# PowerModul.net
KiCad netlist of a schematic drawn in Altium Designer
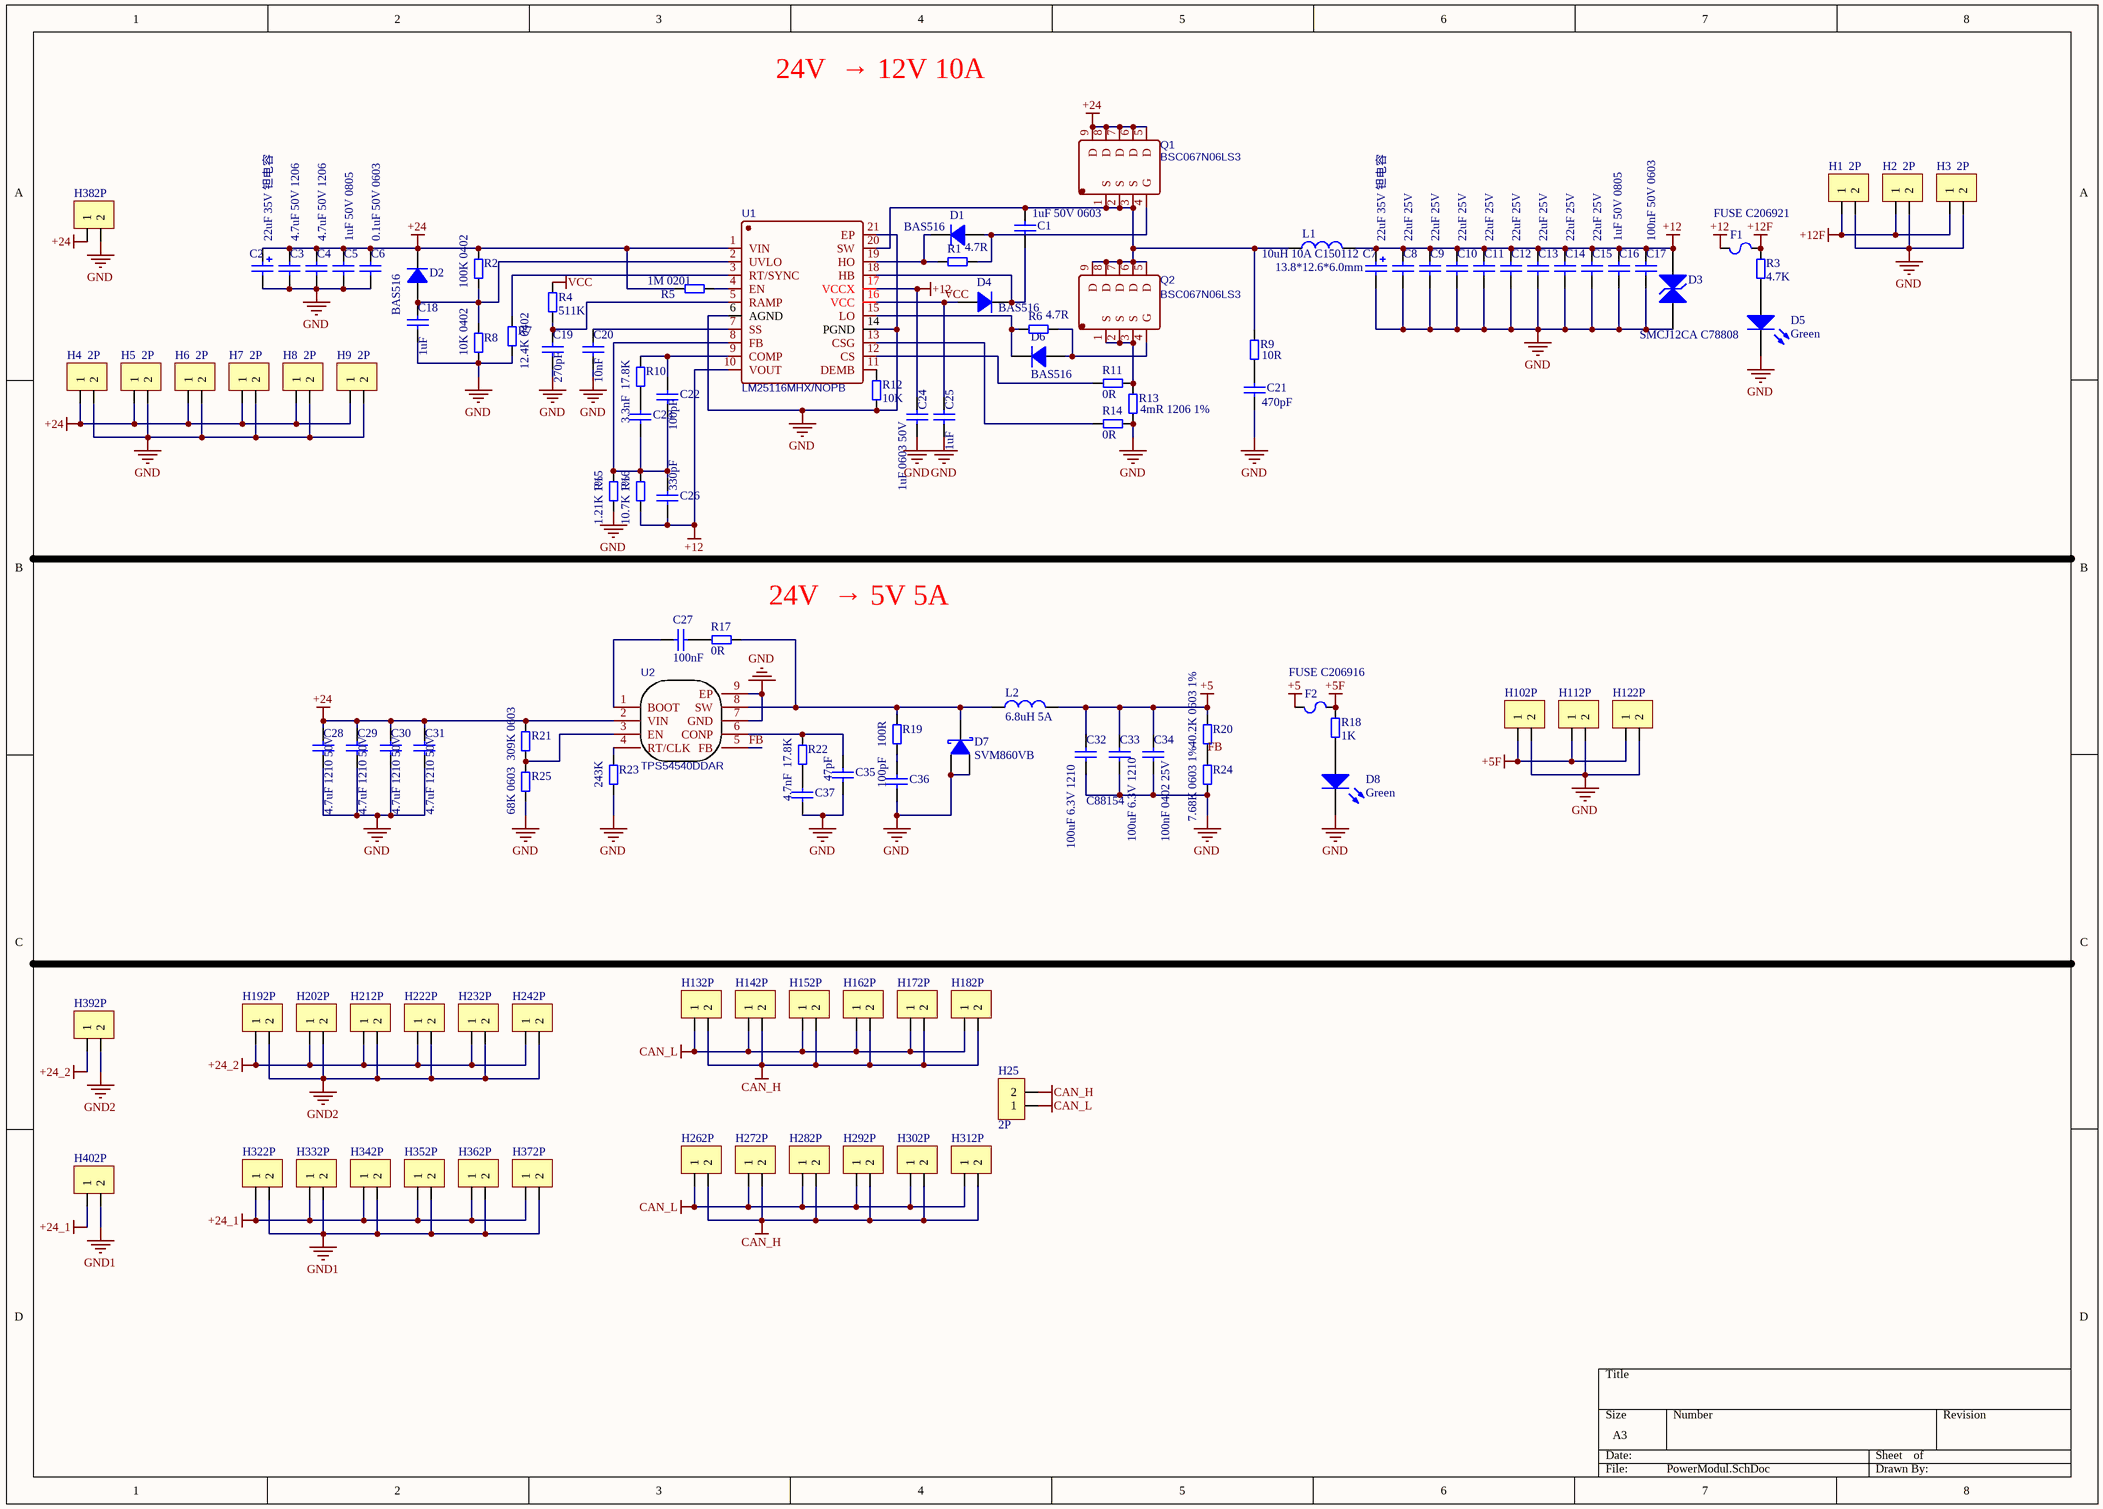
[diagram p0: PowerModul.SchDoc]

(export (version "E")
  (design (tool "Eeschema 10.0.6"))
  (components
    (comp (ref "C1")
      (value "1uF 50V 0603")
      (footprint "0603_C")
      (description "贴片电容")
      (libsource (lib "WTR-SCH_LIB") (part "C"))
    )
    (comp (ref "C2")
      (value "22uF 35V 钽电容")
      (footprint "CAP-SMD_L7.3-W4.3-R-RD")
      (description "极性电容")
      (libsource (lib "WTR-SCH_LIB") (part "Cp"))
    )
    (comp (ref "C3")
      (value "4.7uF 50V 1206")
      (footprint "1206_C")
      (description "贴片电容")
      (libsource (lib "WTR-SCH_LIB") (part "C"))
    )
    (comp (ref "C4")
      (value "4.7uF 50V 1206")
      (footprint "1206_C")
      (description "贴片电容")
      (libsource (lib "WTR-SCH_LIB") (part "C"))
    )
    (comp (ref "C5")
      (value "1uF 50V 0805")
      (footprint "0805_C")
      (description "贴片电容")
      (libsource (lib "WTR-SCH_LIB") (part "C"))
    )
    (comp (ref "C6")
      (value "0.1uF 50V 0603")
      (footprint "0603_C")
      (description "贴片电容")
      (libsource (lib "WTR-SCH_LIB") (part "C"))
    )
    (comp (ref "C7")
      (value "22uF 35V 钽电容")
      (footprint "CAP-SMD_L7.3-W4.3-R-RD")
      (description "极性电容")
      (libsource (lib "WTR-SCH_LIB") (part "Cp"))
    )
    (comp (ref "C8")
      (value "22uF 25V")
      (footprint "1206_C")
      (description "贴片电容")
      (libsource (lib "WTR-SCH_LIB") (part "C"))
    )
    (comp (ref "C9")
      (value "22uF 25V")
      (footprint "1206_C")
      (description "贴片电容")
      (libsource (lib "WTR-SCH_LIB") (part "C"))
    )
    (comp (ref "C10")
      (value "22uF 25V")
      (footprint "1206_C")
      (description "贴片电容")
      (libsource (lib "WTR-SCH_LIB") (part "C"))
    )
    (comp (ref "C11")
      (value "22uF 25V")
      (footprint "1206_C")
      (description "贴片电容")
      (libsource (lib "WTR-SCH_LIB") (part "C"))
    )
    (comp (ref "C12")
      (value "22uF 25V")
      (footprint "1206_C")
      (description "贴片电容")
      (libsource (lib "WTR-SCH_LIB") (part "C"))
    )
    (comp (ref "C13")
      (value "22uF 25V")
      (footprint "1206_C")
      (description "贴片电容")
      (libsource (lib "WTR-SCH_LIB") (part "C"))
    )
    (comp (ref "C14")
      (value "22uF 25V")
      (footprint "1206_C")
      (description "贴片电容")
      (libsource (lib "WTR-SCH_LIB") (part "C"))
    )
    (comp (ref "C15")
      (value "22uF 25V")
      (footprint "1206_C")
      (description "贴片电容")
      (libsource (lib "WTR-SCH_LIB") (part "C"))
    )
    (comp (ref "C16")
      (value "1uF 50V 0805")
      (footprint "0805_C")
      (description "贴片电容")
      (libsource (lib "WTR-SCH_LIB") (part "C"))
    )
    (comp (ref "C17")
      (value "100nF 50V 0603")
      (footprint "0603_C")
      (description "贴片电容")
      (libsource (lib "WTR-SCH_LIB") (part "C"))
    )
    (comp (ref "C18")
      (value "1uF")
      (footprint "0402_C")
      (description "贴片电容")
      (libsource (lib "WTR-SCH_LIB") (part "C"))
    )
    (comp (ref "C19")
      (value "270pF")
      (footprint "0402_C")
      (description "贴片电容")
      (libsource (lib "WTR-SCH_LIB") (part "C"))
    )
    (comp (ref "C20")
      (value "10nF")
      (footprint "0402_C")
      (description "贴片电容")
      (libsource (lib "WTR-SCH_LIB") (part "C"))
    )
    (comp (ref "C21")
      (value "470pF")
      (footprint "0402_C")
      (description "贴片电容")
      (libsource (lib "WTR-SCH_LIB") (part "C"))
    )
    (comp (ref "C22")
      (value "100pF")
      (footprint "0402_C")
      (description "贴片电容")
      (libsource (lib "WTR-SCH_LIB") (part "C"))
    )
    (comp (ref "C23")
      (value "3.3nF")
      (footprint "0402_C")
      (description "贴片电容")
      (libsource (lib "WTR-SCH_LIB") (part "C"))
    )
    (comp (ref "C24")
      (value "1uF 0603 50V")
      (footprint "0603_C")
      (description "贴片电容")
      (libsource (lib "WTR-SCH_LIB") (part "C"))
    )
    (comp (ref "C25")
      (value "1uF")
      (footprint "0402_C")
      (description "贴片电容")
      (libsource (lib "WTR-SCH_LIB") (part "C"))
    )
    (comp (ref "C26")
      (value "330pF")
      (footprint "0402_C")
      (description "贴片电容")
      (libsource (lib "WTR-SCH_LIB") (part "C"))
    )
    (comp (ref "C27")
      (value "100nF")
      (footprint "0402_C")
      (description "贴片电容")
      (libsource (lib "WTR-SCH_LIB") (part "C"))
    )
    (comp (ref "C28")
      (value "4.7uF 1210 50V")
      (footprint "C1210")
      (description "贴片电容")
      (libsource (lib "WTR-SCH_LIB") (part "C"))
    )
    (comp (ref "C29")
      (value "4.7uF 1210 50V")
      (footprint "C1210")
      (description "贴片电容")
      (libsource (lib "WTR-SCH_LIB") (part "C"))
    )
    (comp (ref "C30")
      (value "4.7uF 1210 50V")
      (footprint "C1210")
      (description "贴片电容")
      (libsource (lib "WTR-SCH_LIB") (part "C"))
    )
    (comp (ref "C31")
      (value "4.7uF 1210 50V")
      (footprint "C1210")
      (description "贴片电容")
      (libsource (lib "WTR-SCH_LIB") (part "C"))
    )
    (comp (ref "C32")
      (value "100uF 6.3V 1210")
      (footprint "C1210")
      (description "贴片电容")
      (libsource (lib "WTR-SCH_LIB") (part "C"))
    )
    (comp (ref "C33")
      (value "100uF 6.3V 1210")
      (footprint "C1210")
      (description "贴片电容")
      (libsource (lib "WTR-SCH_LIB") (part "C"))
    )
    (comp (ref "C34")
      (value "100nF 0402 25V")
      (footprint "0402_C")
      (description "贴片电容")
      (libsource (lib "WTR-SCH_LIB") (part "C"))
    )
    (comp (ref "C35")
      (value "47pF")
      (footprint "0603_C")
      (description "贴片电容")
      (libsource (lib "WTR-SCH_LIB") (part "C"))
    )
    (comp (ref "C36")
      (value "100pF")
      (footprint "0603_C")
      (description "贴片电容")
      (libsource (lib "WTR-SCH_LIB") (part "C"))
    )
    (comp (ref "C37")
      (value "4.7nF")
      (footprint "0603_C")
      (description "贴片电容")
      (libsource (lib "WTR-SCH_LIB") (part "C"))
    )
    (comp (ref "D1")
      (value "BAS516")
      (footprint "SOD-523_L1.2-W0.8-LS1.6-RD")
      (description "二极管")
      (libsource (lib "WTR-SCH_LIB") (part "D"))
    )
    (comp (ref "D2")
      (value "BAS516")
      (footprint "SOD-523_L1.2-W0.8-LS1.6-RD")
      (description "二极管")
      (libsource (lib "WTR-SCH_LIB") (part "D"))
    )
    (comp (ref "D3")
      (value "SMCJ12CA C78808")
      (footprint "SMC_L6.9-W5.9-LS7.9-BI")
      (description "TVS")
      (libsource (lib "WTR-SCH_LIB") (part "TVS"))
    )
    (comp (ref "D4")
      (value "BAS516")
      (footprint "SOD-523_L1.2-W0.8-LS1.6-RD")
      (description "二极管")
      (libsource (lib "WTR-SCH_LIB") (part "D"))
    )
    (comp (ref "D5")
      (value "Green")
      (footprint "0805_LED_S1")
      (description "发光二极管")
      (libsource (lib "WTR-SCH_LIB") (part "LED"))
    )
    (comp (ref "D6")
      (value "BAS516")
      (footprint "SOD-523_L1.2-W0.8-LS1.6-RD")
      (description "二极管")
      (libsource (lib "WTR-SCH_LIB") (part "D"))
    )
    (comp (ref "D7")
      (value "SVM860VB")
      (footprint "TO-277B_3P-L6.1-W4.3-LS7.0-BR")
      (description "肖特基二极管")
      (libsource (lib "WTR-SCH_LIB") (part "Ds3"))
    )
    (comp (ref "D8")
      (value "Green")
      (footprint "0805_LED_S1")
      (description "发光二极管")
      (libsource (lib "WTR-SCH_LIB") (part "LED"))
    )
    (comp (ref "F1")
      (value "FUSE C206921")
      (footprint "FUSE-SMD_L9.8-W5.1")
      (description "熔断器")
      (libsource (lib "WTR-SCH_LIB") (part "FUSE"))
    )
    (comp (ref "F2")
      (value "FUSE C206916")
      (footprint "FUSE-SMD_L9.8-W5.1")
      (description "熔断器")
      (libsource (lib "WTR-SCH_LIB") (part "FUSE"))
    )
    (comp (ref "H1") (value "2P") (footprint "XT30UPB-F") (libsource (lib "WTR-SCH_LIB") (part "2P")))
    (comp (ref "H2") (value "2P") (footprint "XT30UPB-F") (libsource (lib "WTR-SCH_LIB") (part "2P")))
    (comp (ref "H3") (value "2P") (footprint "XT30UPB-F") (libsource (lib "WTR-SCH_LIB") (part "2P")))
    (comp (ref "H4") (value "2P") (footprint "XT30UPB-F") (libsource (lib "WTR-SCH_LIB") (part "2P")))
    (comp (ref "H5") (value "2P") (footprint "XT30UPB-F") (libsource (lib "WTR-SCH_LIB") (part "2P")))
    (comp (ref "H6") (value "2P") (footprint "XT30UPB-F") (libsource (lib "WTR-SCH_LIB") (part "2P")))
    (comp (ref "H7") (value "2P") (footprint "XT30UPB-F") (libsource (lib "WTR-SCH_LIB") (part "2P")))
    (comp (ref "H8") (value "2P") (footprint "XT30UPB-F") (libsource (lib "WTR-SCH_LIB") (part "2P")))
    (comp (ref "H9") (value "2P") (footprint "XT30UPB-F") (libsource (lib "WTR-SCH_LIB") (part "2P")))
    (comp (ref "H10") (value "2P") (footprint "XT30UPB-F") (libsource (lib "WTR-SCH_LIB") (part "2P")))
    (comp (ref "H11") (value "2P") (footprint "XT30UPB-F") (libsource (lib "WTR-SCH_LIB") (part "2P")))
    (comp (ref "H12") (value "2P") (footprint "XT30UPB-F") (libsource (lib "WTR-SCH_LIB") (part "2P")))
    (comp (ref "H13") (value "2P") (footprint "GH1.25-S-2P") (libsource (lib "WTR-SCH_LIB") (part "2P")))
    (comp (ref "H14") (value "2P") (footprint "GH1.25-S-2P") (libsource (lib "WTR-SCH_LIB") (part "2P")))
    (comp (ref "H15") (value "2P") (footprint "GH1.25-S-2P") (libsource (lib "WTR-SCH_LIB") (part "2P")))
    (comp (ref "H16") (value "2P") (footprint "GH1.25-S-2P") (libsource (lib "WTR-SCH_LIB") (part "2P")))
    (comp (ref "H17") (value "2P") (footprint "GH1.25-S-2P") (libsource (lib "WTR-SCH_LIB") (part "2P")))
    (comp (ref "H18") (value "2P") (footprint "GH1.25-S-2P") (libsource (lib "WTR-SCH_LIB") (part "2P")))
    (comp (ref "H19") (value "2P") (footprint "TX60-LI-P") (libsource (lib "WTR-SCH_LIB") (part "2P")))
    (comp (ref "H20") (value "2P") (footprint "TX60-LI-P") (libsource (lib "WTR-SCH_LIB") (part "2P")))
    (comp (ref "H21") (value "2P") (footprint "TX60-LI-P") (libsource (lib "WTR-SCH_LIB") (part "2P")))
    (comp (ref "H22") (value "2P") (footprint "TX60-LI-P") (libsource (lib "WTR-SCH_LIB") (part "2P")))
    (comp (ref "H23") (value "2P") (footprint "TX60-LI-P") (libsource (lib "WTR-SCH_LIB") (part "2P")))
    (comp (ref "H24") (value "2P") (footprint "TX60-LI-P") (libsource (lib "WTR-SCH_LIB") (part "2P")))
    (comp (ref "H25") (value "2P") (footprint "GH1.25-S-2P") (libsource (lib "") (part "2P_1")))
    (comp (ref "H26") (value "2P") (footprint "GH1.25-S-2P") (libsource (lib "WTR-SCH_LIB") (part "2P")))
    (comp (ref "H27") (value "2P") (footprint "GH1.25-S-2P") (libsource (lib "WTR-SCH_LIB") (part "2P")))
    (comp (ref "H28") (value "2P") (footprint "GH1.25-S-2P") (libsource (lib "WTR-SCH_LIB") (part "2P")))
    (comp (ref "H29") (value "2P") (footprint "GH1.25-S-2P") (libsource (lib "WTR-SCH_LIB") (part "2P")))
    (comp (ref "H30") (value "2P") (footprint "GH1.25-S-2P") (libsource (lib "WTR-SCH_LIB") (part "2P")))
    (comp (ref "H31") (value "2P") (footprint "GH1.25-S-2P") (libsource (lib "WTR-SCH_LIB") (part "2P")))
    (comp (ref "H32") (value "2P") (footprint "TX60-LI-P") (libsource (lib "WTR-SCH_LIB") (part "2P")))
    (comp (ref "H33") (value "2P") (footprint "TX60-LI-P") (libsource (lib "WTR-SCH_LIB") (part "2P")))
    (comp (ref "H34") (value "2P") (footprint "TX60-LI-P") (libsource (lib "WTR-SCH_LIB") (part "2P")))
    (comp (ref "H35") (value "2P") (footprint "TX60-LI-P") (libsource (lib "WTR-SCH_LIB") (part "2P")))
    (comp (ref "H36") (value "2P") (footprint "TX60-LI-P") (libsource (lib "WTR-SCH_LIB") (part "2P")))
    (comp (ref "H37") (value "2P") (footprint "TX60-LI-P") (libsource (lib "WTR-SCH_LIB") (part "2P")))
    (comp (ref "H38") (value "2P") (footprint "TX60PW-M20") (libsource (lib "WTR-SCH_LIB") (part "2P")))
    (comp (ref "H39") (value "2P") (footprint "TX60PW-M20") (libsource (lib "WTR-SCH_LIB") (part "2P")))
    (comp (ref "H40") (value "2P") (footprint "TX60PW-M20") (libsource (lib "WTR-SCH_LIB") (part "2P")))
    (comp (ref "L1")
      (value "10uH 10A C150112")
      (footprint "IND-SMD_L13.8-W12.6_SMMS1360")
      (description "电感")
      (libsource (lib "WTR-SCH_LIB") (part "L"))
    )
    (comp (ref "L2")
      (value "6.8uH 5A")
      (footprint "IND-SMD_L7.1-W6.6")
      (description "电感")
      (libsource (lib "WTR-SCH_LIB") (part "L"))
    )
    (comp (ref "Q1")
      (value "BSC067N06LS3")
      (footprint "PG-TDSON-8_L5.0-W6.0-P1.27-LS6.2-BL-EP")
      (fields
        (field (name "BOM_SUPPLIER PART") "C140227")
        (field (name "BOM_MANUFACTURER PART") "CSD18563Q5AT")
        (field (name "CONTRIBUTOR") "LCSC")
      )
      (libsource (lib "WTR-SCH_LIB") (part "CSD18563Q5AT"))
    )
    (comp (ref "Q2")
      (value "BSC067N06LS3")
      (footprint "PG-TDSON-8_L5.0-W6.0-P1.27-LS6.2-BL-EP")
      (fields
        (field (name "BOM_SUPPLIER PART") "C140227")
        (field (name "BOM_MANUFACTURER PART") "CSD18563Q5AT")
        (field (name "CONTRIBUTOR") "LCSC")
      )
      (libsource (lib "WTR-SCH_LIB") (part "CSD18563Q5AT"))
    )
    (comp (ref "R1")
      (value "4.7R")
      (footprint "0402_R")
      (description "贴片电阻")
      (libsource (lib "WTR-SCH_LIB") (part "R"))
    )
    (comp (ref "R2")
      (value "100K 0402")
      (footprint "0402_R")
      (description "贴片电阻")
      (libsource (lib "WTR-SCH_LIB") (part "R"))
    )
    (comp (ref "R3")
      (value "4.7K")
      (footprint "0402_R")
      (description "贴片电阻")
      (libsource (lib "WTR-SCH_LIB") (part "R"))
    )
    (comp (ref "R4")
      (value "511K")
      (footprint "0402_R")
      (description "贴片电阻")
      (libsource (lib "WTR-SCH_LIB") (part "R"))
    )
    (comp (ref "R5")
      (value "1M 0201")
      (footprint "0402_R")
      (description "贴片电阻")
      (libsource (lib "WTR-SCH_LIB") (part "R"))
    )
    (comp (ref "R6")
      (value "4.7R")
      (footprint "0402_R")
      (description "贴片电阻")
      (libsource (lib "WTR-SCH_LIB") (part "R"))
    )
    (comp (ref "R7")
      (value "12.4K 0402")
      (footprint "0402_R")
      (description "贴片电阻")
      (libsource (lib "WTR-SCH_LIB") (part "R"))
    )
    (comp (ref "R8")
      (value "10K 0402")
      (footprint "0402_R")
      (description "贴片电阻")
      (libsource (lib "WTR-SCH_LIB") (part "R"))
    )
    (comp (ref "R9")
      (value "10R")
      (footprint "0402_R")
      (description "贴片电阻")
      (libsource (lib "WTR-SCH_LIB") (part "R"))
    )
    (comp (ref "R10")
      (value "17.8K")
      (footprint "0402_R")
      (description "贴片电阻")
      (libsource (lib "WTR-SCH_LIB") (part "R"))
    )
    (comp (ref "R11")
      (value "0R")
      (footprint "0402_R")
      (description "贴片电阻")
      (libsource (lib "WTR-SCH_LIB") (part "R"))
    )
    (comp (ref "R12")
      (value "10K")
      (footprint "0402_R")
      (description "贴片电阻")
      (libsource (lib "WTR-SCH_LIB") (part "R"))
    )
    (comp (ref "R13")
      (value "4mR 1206 1%")
      (footprint "1206_R")
      (description "贴片电阻")
      (libsource (lib "WTR-SCH_LIB") (part "R"))
    )
    (comp (ref "R14")
      (value "0R")
      (footprint "0402_R")
      (description "贴片电阻")
      (libsource (lib "WTR-SCH_LIB") (part "R"))
    )
    (comp (ref "R15")
      (value "1.21K 1%")
      (footprint "0402_R")
      (description "贴片电阻")
      (libsource (lib "WTR-SCH_LIB") (part "R"))
    )
    (comp (ref "R16")
      (value "10.7K 1%")
      (footprint "0402_R")
      (description "贴片电阻")
      (libsource (lib "WTR-SCH_LIB") (part "R"))
    )
    (comp (ref "R17")
      (value "0R")
      (footprint "0402_R")
      (description "贴片电阻")
      (libsource (lib "WTR-SCH_LIB") (part "R"))
    )
    (comp (ref "R18")
      (value "1K")
      (footprint "0402_R")
      (description "贴片电阻")
      (libsource (lib "WTR-SCH_LIB") (part "R"))
    )
    (comp (ref "R19")
      (value "100R")
      (footprint "0402_R")
      (description "贴片电阻")
      (libsource (lib "WTR-SCH_LIB") (part "R"))
    )
    (comp (ref "R20")
      (value "40.2K 0603 1%")
      (footprint "0603_R")
      (description "贴片电阻")
      (libsource (lib "WTR-SCH_LIB") (part "R"))
    )
    (comp (ref "R21")
      (value "309K 0603")
      (footprint "0603_R")
      (description "贴片电阻")
      (libsource (lib "WTR-SCH_LIB") (part "R"))
    )
    (comp (ref "R22")
      (value "17.8K")
      (footprint "0402_R")
      (description "贴片电阻")
      (libsource (lib "WTR-SCH_LIB") (part "R"))
    )
    (comp (ref "R23")
      (value "243K")
      (footprint "0402_R")
      (description "贴片电阻")
      (libsource (lib "WTR-SCH_LIB") (part "R"))
    )
    (comp (ref "R24")
      (value "7.68K 0603 1%")
      (footprint "0603_R")
      (description "贴片电阻")
      (libsource (lib "WTR-SCH_LIB") (part "R"))
    )
    (comp (ref "R25")
      (value "68K 0603")
      (footprint "0603_R")
      (description "贴片电阻")
      (libsource (lib "WTR-SCH_LIB") (part "R"))
    )
    (comp (ref "U1")
      (value "LM25116MHX/NOPB")
      (footprint "HTSSOP-20_L6.5-W4.4-P0.65-LS6.4-BL-EP")
      (fields (field (name "BOM_SUPPLIER PART") "C390951") (field (name "CONTRIBUTOR") "LCSC"))
      (libsource (lib "Sheet_2_2020-07-13_16-15-20") (part "LM25116MHX/NOPB"))
    )
    (comp (ref "U2")
      (value "TPS54540DDAR")
      (footprint "SOIC-8-EP")
      (fields (field (name "BOM_SUPPLIER PART") "C95286"))
      (libsource (lib "WTR-SCH_LIB") (part "TPS54540DDAR"))
    )
  )
  (nets
    (net (code "1") (name "+5") (class "Default")
      (node (ref "C32") (pin "2") (pinfunction "2_2") (pintype "passive"))
      (node (ref "C33") (pin "2") (pinfunction "2_2") (pintype "passive"))
      (node (ref "C34") (pin "2") (pinfunction "2_2") (pintype "passive"))
      (node (ref "F2") (pin "1") (pinfunction "1_1") (pintype "passive"))
      (node (ref "L2") (pin "2") (pinfunction "2_2") (pintype "passive"))
      (node (ref "R20") (pin "1") (pinfunction "1_1") (pintype "passive"))
    )
    (net (code "2") (name "+5F") (class "Default")
      (node (ref "F2") (pin "2") (pinfunction "2_2") (pintype "passive"))
      (node (ref "H10") (pin "1") (pinfunction "1_1") (pintype "passive"))
      (node (ref "H11") (pin "1") (pinfunction "1_1") (pintype "passive"))
      (node (ref "H12") (pin "1") (pinfunction "1_1") (pintype "passive"))
      (node (ref "R18") (pin "1") (pinfunction "1_1") (pintype "passive"))
    )
    (net (code "3") (name "+12") (class "Default")
      (node (ref "C10") (pin "2") (pinfunction "2_2") (pintype "passive"))
      (node (ref "C11") (pin "2") (pinfunction "2_2") (pintype "passive"))
      (node (ref "C12") (pin "2") (pinfunction "2_2") (pintype "passive"))
      (node (ref "C13") (pin "2") (pinfunction "2_2") (pintype "passive"))
      (node (ref "C14") (pin "2") (pinfunction "2_2") (pintype "passive"))
      (node (ref "C15") (pin "2") (pinfunction "2_2") (pintype "passive"))
      (node (ref "C16") (pin "2") (pinfunction "2_2") (pintype "passive"))
      (node (ref "C17") (pin "2") (pinfunction "2_2") (pintype "passive"))
      (node (ref "C24") (pin "2") (pinfunction "2_2") (pintype "passive"))
      (node (ref "C26") (pin "1") (pinfunction "1_1") (pintype "passive"))
      (node (ref "C7") (pin "1") (pinfunction "1_1") (pintype "passive"))
      (node (ref "C8") (pin "2") (pinfunction "2_2") (pintype "passive"))
      (node (ref "C9") (pin "2") (pinfunction "2_2") (pintype "passive"))
      (node (ref "D3") (pin "2") (pinfunction "K_2") (pintype "passive"))
      (node (ref "F1") (pin "1") (pinfunction "1_1") (pintype "passive"))
      (node (ref "L1") (pin "2") (pinfunction "2_2") (pintype "passive"))
      (node (ref "R16") (pin "2") (pinfunction "2_2") (pintype "passive"))
      (node (ref "U1") (pin "10") (pinfunction "VOUT_10") (pintype "passive"))
      (node (ref "U1") (pin "17") (pinfunction "VCCX_17") (pintype "passive"))
    )
    (net (code "4") (name "+12F") (class "Default")
      (node (ref "F1") (pin "2") (pinfunction "2_2") (pintype "passive"))
      (node (ref "H1") (pin "1") (pinfunction "1_1") (pintype "passive"))
      (node (ref "H2") (pin "1") (pinfunction "1_1") (pintype "passive"))
      (node (ref "H3") (pin "1") (pinfunction "1_1") (pintype "passive"))
      (node (ref "R3") (pin "1") (pinfunction "1_1") (pintype "passive"))
    )
    (net (code "5") (name "+24") (class "Default")
      (node (ref "C2") (pin "1") (pinfunction "1_1") (pintype "passive"))
      (node (ref "C28") (pin "2") (pinfunction "2_2") (pintype "passive"))
      (node (ref "C29") (pin "2") (pinfunction "2_2") (pintype "passive"))
      (node (ref "C3") (pin "2") (pinfunction "2_2") (pintype "passive"))
      (node (ref "C30") (pin "2") (pinfunction "2_2") (pintype "passive"))
      (node (ref "C31") (pin "2") (pinfunction "2_2") (pintype "passive"))
      (node (ref "C4") (pin "2") (pinfunction "2_2") (pintype "passive"))
      (node (ref "C5") (pin "2") (pinfunction "2_2") (pintype "passive"))
      (node (ref "C6") (pin "2") (pinfunction "2_2") (pintype "passive"))
      (node (ref "D2") (pin "2") (pinfunction "K_2") (pintype "passive"))
      (node (ref "H38") (pin "1") (pinfunction "1_1") (pintype "passive"))
      (node (ref "H4") (pin "1") (pinfunction "1_1") (pintype "passive"))
      (node (ref "H5") (pin "1") (pinfunction "1_1") (pintype "passive"))
      (node (ref "H6") (pin "1") (pinfunction "1_1") (pintype "passive"))
      (node (ref "H7") (pin "1") (pinfunction "1_1") (pintype "passive"))
      (node (ref "H8") (pin "1") (pinfunction "1_1") (pintype "passive"))
      (node (ref "H9") (pin "1") (pinfunction "1_1") (pintype "passive"))
      (node (ref "Q1") (pin "5") (pinfunction "D_5") (pintype "passive"))
      (node (ref "Q1") (pin "6") (pinfunction "D_6") (pintype "passive"))
      (node (ref "Q1") (pin "7") (pinfunction "D_7") (pintype "passive"))
      (node (ref "Q1") (pin "8") (pinfunction "D_8") (pintype "passive"))
      (node (ref "Q1") (pin "9") (pinfunction "D_9") (pintype "passive"))
      (node (ref "R2") (pin "2") (pinfunction "2_2") (pintype "passive"))
      (node (ref "R21") (pin "2") (pinfunction "2_2") (pintype "passive"))
      (node (ref "R5") (pin "2") (pinfunction "2_2") (pintype "passive"))
      (node (ref "U1") (pin "1") (pinfunction "VIN_1") (pintype "passive"))
      (node (ref "U2") (pin "2") (pinfunction "VIN_2") (pintype "passive"))
    )
    (net (code "6") (name "+24_1") (class "Default")
      (node (ref "H32") (pin "1") (pinfunction "1_1") (pintype "passive"))
      (node (ref "H33") (pin "1") (pinfunction "1_1") (pintype "passive"))
      (node (ref "H34") (pin "1") (pinfunction "1_1") (pintype "passive"))
      (node (ref "H35") (pin "1") (pinfunction "1_1") (pintype "passive"))
      (node (ref "H36") (pin "1") (pinfunction "1_1") (pintype "passive"))
      (node (ref "H37") (pin "1") (pinfunction "1_1") (pintype "passive"))
      (node (ref "H40") (pin "1") (pinfunction "1_1") (pintype "passive"))
    )
    (net (code "7") (name "+24_2") (class "Default")
      (node (ref "H19") (pin "1") (pinfunction "1_1") (pintype "passive"))
      (node (ref "H20") (pin "1") (pinfunction "1_1") (pintype "passive"))
      (node (ref "H21") (pin "1") (pinfunction "1_1") (pintype "passive"))
      (node (ref "H22") (pin "1") (pinfunction "1_1") (pintype "passive"))
      (node (ref "H23") (pin "1") (pinfunction "1_1") (pintype "passive"))
      (node (ref "H24") (pin "1") (pinfunction "1_1") (pintype "passive"))
      (node (ref "H39") (pin "1") (pinfunction "1_1") (pintype "passive"))
    )
    (net (code "8") (name "/FB") (class "Default")
      (node (ref "R20") (pin "2") (pinfunction "2_2") (pintype "passive"))
      (node (ref "R24") (pin "1") (pinfunction "1_1") (pintype "passive"))
      (node (ref "U2") (pin "5") (pinfunction "FB_5") (pintype "passive"))
    )
    (net (code "9") (name "CAN_H") (class "Default")
      (node (ref "H13") (pin "2") (pinfunction "2_2") (pintype "passive"))
      (node (ref "H14") (pin "2") (pinfunction "2_2") (pintype "passive"))
      (node (ref "H15") (pin "2") (pinfunction "2_2") (pintype "passive"))
      (node (ref "H16") (pin "2") (pinfunction "2_2") (pintype "passive"))
      (node (ref "H17") (pin "2") (pinfunction "2_2") (pintype "passive"))
      (node (ref "H18") (pin "2") (pinfunction "2_2") (pintype "passive"))
      (node (ref "H25") (pin "2") (pinfunction "2_2") (pintype "passive"))
      (node (ref "H26") (pin "2") (pinfunction "2_2") (pintype "passive"))
      (node (ref "H27") (pin "2") (pinfunction "2_2") (pintype "passive"))
      (node (ref "H28") (pin "2") (pinfunction "2_2") (pintype "passive"))
      (node (ref "H29") (pin "2") (pinfunction "2_2") (pintype "passive"))
      (node (ref "H30") (pin "2") (pinfunction "2_2") (pintype "passive"))
      (node (ref "H31") (pin "2") (pinfunction "2_2") (pintype "passive"))
    )
    (net (code "10") (name "CAN_L") (class "Default")
      (node (ref "H13") (pin "1") (pinfunction "1_1") (pintype "passive"))
      (node (ref "H14") (pin "1") (pinfunction "1_1") (pintype "passive"))
      (node (ref "H15") (pin "1") (pinfunction "1_1") (pintype "passive"))
      (node (ref "H16") (pin "1") (pinfunction "1_1") (pintype "passive"))
      (node (ref "H17") (pin "1") (pinfunction "1_1") (pintype "passive"))
      (node (ref "H18") (pin "1") (pinfunction "1_1") (pintype "passive"))
      (node (ref "H25") (pin "1") (pinfunction "1_1") (pintype "passive"))
      (node (ref "H26") (pin "1") (pinfunction "1_1") (pintype "passive"))
      (node (ref "H27") (pin "1") (pinfunction "1_1") (pintype "passive"))
      (node (ref "H28") (pin "1") (pinfunction "1_1") (pintype "passive"))
      (node (ref "H29") (pin "1") (pinfunction "1_1") (pintype "passive"))
      (node (ref "H30") (pin "1") (pinfunction "1_1") (pintype "passive"))
      (node (ref "H31") (pin "1") (pinfunction "1_1") (pintype "passive"))
    )
    (net (code "11") (name "GND") (class "Default")
      (node (ref "C10") (pin "1") (pinfunction "1_1") (pintype "passive"))
      (node (ref "C11") (pin "1") (pinfunction "1_1") (pintype "passive"))
      (node (ref "C12") (pin "1") (pinfunction "1_1") (pintype "passive"))
      (node (ref "C13") (pin "1") (pinfunction "1_1") (pintype "passive"))
      (node (ref "C14") (pin "1") (pinfunction "1_1") (pintype "passive"))
      (node (ref "C15") (pin "1") (pinfunction "1_1") (pintype "passive"))
      (node (ref "C16") (pin "1") (pinfunction "1_1") (pintype "passive"))
      (node (ref "C17") (pin "1") (pinfunction "1_1") (pintype "passive"))
      (node (ref "C18") (pin "1") (pinfunction "1_1") (pintype "passive"))
      (node (ref "C19") (pin "1") (pinfunction "1_1") (pintype "passive"))
      (node (ref "C2") (pin "2") (pinfunction "2_2") (pintype "passive"))
      (node (ref "C20") (pin "1") (pinfunction "1_1") (pintype "passive"))
      (node (ref "C21") (pin "1") (pinfunction "1_1") (pintype "passive"))
      (node (ref "C24") (pin "1") (pinfunction "1_1") (pintype "passive"))
      (node (ref "C25") (pin "1") (pinfunction "1_1") (pintype "passive"))
      (node (ref "C28") (pin "1") (pinfunction "1_1") (pintype "passive"))
      (node (ref "C29") (pin "1") (pinfunction "1_1") (pintype "passive"))
      (node (ref "C3") (pin "1") (pinfunction "1_1") (pintype "passive"))
      (node (ref "C30") (pin "1") (pinfunction "1_1") (pintype "passive"))
      (node (ref "C31") (pin "1") (pinfunction "1_1") (pintype "passive"))
      (node (ref "C32") (pin "1") (pinfunction "1_1") (pintype "passive"))
      (node (ref "C33") (pin "1") (pinfunction "1_1") (pintype "passive"))
      (node (ref "C34") (pin "1") (pinfunction "1_1") (pintype "passive"))
      (node (ref "C35") (pin "1") (pinfunction "1_1") (pintype "passive"))
      (node (ref "C36") (pin "1") (pinfunction "1_1") (pintype "passive"))
      (node (ref "C37") (pin "1") (pinfunction "1_1") (pintype "passive"))
      (node (ref "C4") (pin "1") (pinfunction "1_1") (pintype "passive"))
      (node (ref "C5") (pin "1") (pinfunction "1_1") (pintype "passive"))
      (node (ref "C6") (pin "1") (pinfunction "1_1") (pintype "passive"))
      (node (ref "C7") (pin "2") (pinfunction "2_2") (pintype "passive"))
      (node (ref "C8") (pin "1") (pinfunction "1_1") (pintype "passive"))
      (node (ref "C9") (pin "1") (pinfunction "1_1") (pintype "passive"))
      (node (ref "D3") (pin "1") (pinfunction "A_1") (pintype "passive"))
      (node (ref "D5") (pin "K") (pinfunction "K_K") (pintype "passive"))
      (node (ref "D7") (pin "1") (pinfunction "A_1") (pintype "passive"))
      (node (ref "D7") (pin "2") (pinfunction "A_2") (pintype "passive"))
      (node (ref "D8") (pin "K") (pinfunction "K_K") (pintype "passive"))
      (node (ref "H1") (pin "2") (pinfunction "2_2") (pintype "passive"))
      (node (ref "H10") (pin "2") (pinfunction "2_2") (pintype "passive"))
      (node (ref "H11") (pin "2") (pinfunction "2_2") (pintype "passive"))
      (node (ref "H12") (pin "2") (pinfunction "2_2") (pintype "passive"))
      (node (ref "H2") (pin "2") (pinfunction "2_2") (pintype "passive"))
      (node (ref "H3") (pin "2") (pinfunction "2_2") (pintype "passive"))
      (node (ref "H38") (pin "2") (pinfunction "2_2") (pintype "passive"))
      (node (ref "H4") (pin "2") (pinfunction "2_2") (pintype "passive"))
      (node (ref "H5") (pin "2") (pinfunction "2_2") (pintype "passive"))
      (node (ref "H6") (pin "2") (pinfunction "2_2") (pintype "passive"))
      (node (ref "H7") (pin "2") (pinfunction "2_2") (pintype "passive"))
      (node (ref "H8") (pin "2") (pinfunction "2_2") (pintype "passive"))
      (node (ref "H9") (pin "2") (pinfunction "2_2") (pintype "passive"))
      (node (ref "R12") (pin "1") (pinfunction "1_1") (pintype "passive"))
      (node (ref "R13") (pin "2") (pinfunction "2_2") (pintype "passive"))
      (node (ref "R14") (pin "2") (pinfunction "2_2") (pintype "passive"))
      (node (ref "R15") (pin "1") (pinfunction "1_1") (pintype "passive"))
      (node (ref "R23") (pin "1") (pinfunction "1_1") (pintype "passive"))
      (node (ref "R24") (pin "2") (pinfunction "2_2") (pintype "passive"))
      (node (ref "R25") (pin "1") (pinfunction "1_1") (pintype "passive"))
      (node (ref "R7") (pin "1") (pinfunction "1_1") (pintype "passive"))
      (node (ref "R8") (pin "1") (pinfunction "1_1") (pintype "passive"))
      (node (ref "U1") (pin "14") (pinfunction "PGND_14") (pintype "passive"))
      (node (ref "U1") (pin "21") (pinfunction "EP_21") (pintype "passive"))
      (node (ref "U1") (pin "6") (pinfunction "AGND_6") (pintype "passive"))
      (node (ref "U2") (pin "7") (pinfunction "GND_7") (pintype "passive"))
      (node (ref "U2") (pin "9") (pinfunction "EP_9") (pintype "passive"))
    )
    (net (code "12") (name "GND1") (class "Default")
      (node (ref "H32") (pin "2") (pinfunction "2_2") (pintype "passive"))
      (node (ref "H33") (pin "2") (pinfunction "2_2") (pintype "passive"))
      (node (ref "H34") (pin "2") (pinfunction "2_2") (pintype "passive"))
      (node (ref "H35") (pin "2") (pinfunction "2_2") (pintype "passive"))
      (node (ref "H36") (pin "2") (pinfunction "2_2") (pintype "passive"))
      (node (ref "H37") (pin "2") (pinfunction "2_2") (pintype "passive"))
      (node (ref "H40") (pin "2") (pinfunction "2_2") (pintype "passive"))
    )
    (net (code "13") (name "GND2") (class "Default")
      (node (ref "H19") (pin "2") (pinfunction "2_2") (pintype "passive"))
      (node (ref "H20") (pin "2") (pinfunction "2_2") (pintype "passive"))
      (node (ref "H21") (pin "2") (pinfunction "2_2") (pintype "passive"))
      (node (ref "H22") (pin "2") (pinfunction "2_2") (pintype "passive"))
      (node (ref "H23") (pin "2") (pinfunction "2_2") (pintype "passive"))
      (node (ref "H24") (pin "2") (pinfunction "2_2") (pintype "passive"))
      (node (ref "H39") (pin "2") (pinfunction "2_2") (pintype "passive"))
    )
    (net (code "14") (name "Net-(C21-Pad2)") (class "Default")
      (node (ref "C21") (pin "2") (pinfunction "2_2") (pintype "passive"))
      (node (ref "R9") (pin "2") (pinfunction "2_2") (pintype "passive"))
    )
    (net (code "15") (name "Net-(C23-Pad2)") (class "Default")
      (node (ref "C23") (pin "2") (pinfunction "2_2") (pintype "passive"))
      (node (ref "R10") (pin "2") (pinfunction "2_2") (pintype "passive"))
    )
    (net (code "16") (name "Net-(C27-Pad1)") (class "Default")
      (node (ref "C27") (pin "1") (pinfunction "1_1") (pintype "passive"))
      (node (ref "R17") (pin "1") (pinfunction "1_1") (pintype "passive"))
    )
    (net (code "17") (name "Net-(C36-Pad2)") (class "Default")
      (node (ref "C36") (pin "2") (pinfunction "2_2") (pintype "passive"))
      (node (ref "R19") (pin "2") (pinfunction "2_2") (pintype "passive"))
    )
    (net (code "18") (name "Net-(C37-Pad2)") (class "Default")
      (node (ref "C37") (pin "2") (pinfunction "2_2") (pintype "passive"))
      (node (ref "R22") (pin "2") (pinfunction "2_2") (pintype "passive"))
    )
    (net (code "19") (name "Net-(D1-A)") (class "Default")
      (node (ref "D1") (pin "1") (pinfunction "A_1") (pintype "passive"))
      (node (ref "Q1") (pin "4") (pinfunction "G_4") (pintype "passive"))
      (node (ref "R1") (pin "1") (pinfunction "1_1") (pintype "passive"))
    )
    (net (code "20") (name "Net-(D1-K)") (class "Default")
      (node (ref "D1") (pin "2") (pinfunction "K_2") (pintype "passive"))
      (node (ref "R1") (pin "2") (pinfunction "2_2") (pintype "passive"))
      (node (ref "U1") (pin "19") (pinfunction "HO_19") (pintype "passive"))
    )
    (net (code "21") (name "Net-(D2-A)") (class "Default")
      (node (ref "C18") (pin "2") (pinfunction "2_2") (pintype "passive"))
      (node (ref "D2") (pin "1") (pinfunction "A_1") (pintype "passive"))
      (node (ref "R2") (pin "1") (pinfunction "1_1") (pintype "passive"))
      (node (ref "R8") (pin "2") (pinfunction "2_2") (pintype "passive"))
      (node (ref "U1") (pin "2") (pinfunction "UVLO_2") (pintype "passive"))
    )
    (net (code "22") (name "Net-(D4-K)") (class "Default")
      (node (ref "C1") (pin "1") (pinfunction "1_1") (pintype "passive"))
      (node (ref "D4") (pin "2") (pinfunction "K_2") (pintype "passive"))
      (node (ref "U1") (pin "18") (pinfunction "HB_18") (pintype "passive"))
    )
    (net (code "23") (name "Net-(D5-PadA)") (class "Default")
      (node (ref "D5") (pin "A") (pinfunction "A_A") (pintype "passive"))
      (node (ref "R3") (pin "2") (pinfunction "2_2") (pintype "passive"))
    )
    (net (code "24") (name "Net-(D6-A)") (class "Default")
      (node (ref "D6") (pin "1") (pinfunction "A_1") (pintype "passive"))
      (node (ref "Q2") (pin "4") (pinfunction "G_4") (pintype "passive"))
      (node (ref "R6") (pin "1") (pinfunction "1_1") (pintype "passive"))
    )
    (net (code "25") (name "Net-(D6-K)") (class "Default")
      (node (ref "D6") (pin "2") (pinfunction "K_2") (pintype "passive"))
      (node (ref "R6") (pin "2") (pinfunction "2_2") (pintype "passive"))
      (node (ref "U1") (pin "15") (pinfunction "LO_15") (pintype "passive"))
    )
    (net (code "26") (name "Net-(D7-K)") (class "Default")
      (node (ref "D7") (pin "3") (pinfunction "K_3") (pintype "passive"))
      (node (ref "L2") (pin "1") (pinfunction "1_1") (pintype "passive"))
      (node (ref "R17") (pin "2") (pinfunction "2_2") (pintype "passive"))
      (node (ref "R19") (pin "1") (pinfunction "1_1") (pintype "passive"))
      (node (ref "U2") (pin "8") (pinfunction "SW_8") (pintype "passive"))
    )
    (net (code "27") (name "Net-(D8-PadA)") (class "Default")
      (node (ref "D8") (pin "A") (pinfunction "A_A") (pintype "passive"))
      (node (ref "R18") (pin "2") (pinfunction "2_2") (pintype "passive"))
    )
    (net (code "28") (name "Net-(Q2-S-Pad1)") (class "Default")
      (node (ref "Q2") (pin "1") (pinfunction "S_1") (pintype "passive"))
      (node (ref "Q2") (pin "2") (pinfunction "S_2") (pintype "passive"))
      (node (ref "Q2") (pin "3") (pinfunction "S_3") (pintype "passive"))
      (node (ref "R11") (pin "2") (pinfunction "2_2") (pintype "passive"))
      (node (ref "R13") (pin "1") (pinfunction "1_1") (pintype "passive"))
    )
    (net (code "29") (name "Net-(U1-COMP)") (class "Default")
      (node (ref "C22") (pin "2") (pinfunction "2_2") (pintype "passive"))
      (node (ref "R10") (pin "1") (pinfunction "1_1") (pintype "passive"))
      (node (ref "U1") (pin "9") (pinfunction "COMP_9") (pintype "passive"))
    )
    (net (code "30") (name "Net-(U1-CS)") (class "Default")
      (node (ref "R11") (pin "1") (pinfunction "1_1") (pintype "passive"))
      (node (ref "U1") (pin "12") (pinfunction "CS_12") (pintype "passive"))
    )
    (net (code "31") (name "Net-(U1-CSG)") (class "Default")
      (node (ref "R14") (pin "1") (pinfunction "1_1") (pintype "passive"))
      (node (ref "U1") (pin "13") (pinfunction "CSG_13") (pintype "passive"))
    )
    (net (code "32") (name "Net-(U1-DEMB)") (class "Default")
      (node (ref "R12") (pin "2") (pinfunction "2_2") (pintype "passive"))
      (node (ref "U1") (pin "11") (pinfunction "DEMB_11") (pintype "passive"))
    )
    (net (code "33") (name "Net-(U1-EN)") (class "Default")
      (node (ref "R5") (pin "1") (pinfunction "1_1") (pintype "passive"))
      (node (ref "U1") (pin "4") (pinfunction "EN_4") (pintype "passive"))
    )
    (net (code "34") (name "Net-(U1-FB)") (class "Default")
      (node (ref "C22") (pin "1") (pinfunction "1_1") (pintype "passive"))
      (node (ref "C23") (pin "1") (pinfunction "1_1") (pintype "passive"))
      (node (ref "C26") (pin "2") (pinfunction "2_2") (pintype "passive"))
      (node (ref "R15") (pin "2") (pinfunction "2_2") (pintype "passive"))
      (node (ref "R16") (pin "1") (pinfunction "1_1") (pintype "passive"))
      (node (ref "U1") (pin "8") (pinfunction "FB_8") (pintype "passive"))
    )
    (net (code "35") (name "Net-(U1-RAMP)") (class "Default")
      (node (ref "C19") (pin "2") (pinfunction "2_2") (pintype "passive"))
      (node (ref "R4") (pin "1") (pinfunction "1_1") (pintype "passive"))
      (node (ref "U1") (pin "5") (pinfunction "RAMP_5") (pintype "passive"))
    )
    (net (code "36") (name "Net-(U1-RT{slash}SYNC)") (class "Default")
      (node (ref "R7") (pin "2") (pinfunction "2_2") (pintype "passive"))
      (node (ref "U1") (pin "3") (pinfunction "RT/SYNC_3") (pintype "passive"))
    )
    (net (code "37") (name "Net-(U1-SS)") (class "Default")
      (node (ref "C20") (pin "2") (pinfunction "2_2") (pintype "passive"))
      (node (ref "U1") (pin "7") (pinfunction "SS_7") (pintype "passive"))
    )
    (net (code "38") (name "Net-(U1-SW)") (class "Default")
      (node (ref "C1") (pin "2") (pinfunction "2_2") (pintype "passive"))
      (node (ref "L1") (pin "1") (pinfunction "1_1") (pintype "passive"))
      (node (ref "Q1") (pin "1") (pinfunction "S_1") (pintype "passive"))
      (node (ref "Q1") (pin "2") (pinfunction "S_2") (pintype "passive"))
      (node (ref "Q1") (pin "3") (pinfunction "S_3") (pintype "passive"))
      (node (ref "Q2") (pin "5") (pinfunction "D_5") (pintype "passive"))
      (node (ref "Q2") (pin "6") (pinfunction "D_6") (pintype "passive"))
      (node (ref "Q2") (pin "7") (pinfunction "D_7") (pintype "passive"))
      (node (ref "Q2") (pin "8") (pinfunction "D_8") (pintype "passive"))
      (node (ref "Q2") (pin "9") (pinfunction "D_9") (pintype "passive"))
      (node (ref "R9") (pin "1") (pinfunction "1_1") (pintype "passive"))
      (node (ref "U1") (pin "20") (pinfunction "SW_20") (pintype "passive"))
    )
    (net (code "39") (name "Net-(U2-BOOT)") (class "Default")
      (node (ref "C27") (pin "2") (pinfunction "2_2") (pintype "passive"))
      (node (ref "U2") (pin "1") (pinfunction "BOOT_1") (pintype "passive"))
    )
    (net (code "40") (name "Net-(U2-CONP)") (class "Default")
      (node (ref "C35") (pin "2") (pinfunction "2_2") (pintype "passive"))
      (node (ref "R22") (pin "1") (pinfunction "1_1") (pintype "passive"))
      (node (ref "U2") (pin "6") (pinfunction "CONP_6") (pintype "passive"))
    )
    (net (code "41") (name "Net-(U2-EN)") (class "Default")
      (node (ref "R21") (pin "1") (pinfunction "1_1") (pintype "passive"))
      (node (ref "R25") (pin "2") (pinfunction "2_2") (pintype "passive"))
      (node (ref "U2") (pin "3") (pinfunction "EN_3") (pintype "passive"))
    )
    (net (code "42") (name "Net-(U2-RT{slash}CLK)") (class "Default")
      (node (ref "R23") (pin "2") (pinfunction "2_2") (pintype "passive"))
      (node (ref "U2") (pin "4") (pinfunction "RT/CLK_4") (pintype "passive"))
    )
    (net (code "43") (name "VCC") (class "Default")
      (node (ref "C25") (pin "2") (pinfunction "2_2") (pintype "passive"))
      (node (ref "D4") (pin "1") (pinfunction "A_1") (pintype "passive"))
      (node (ref "R4") (pin "2") (pinfunction "2_2") (pintype "passive"))
      (node (ref "U1") (pin "16") (pinfunction "VCC_16") (pintype "passive"))
    )
  )
)
